# mainboard.net
KiCad netlist of a schematic drawn in EAGLE
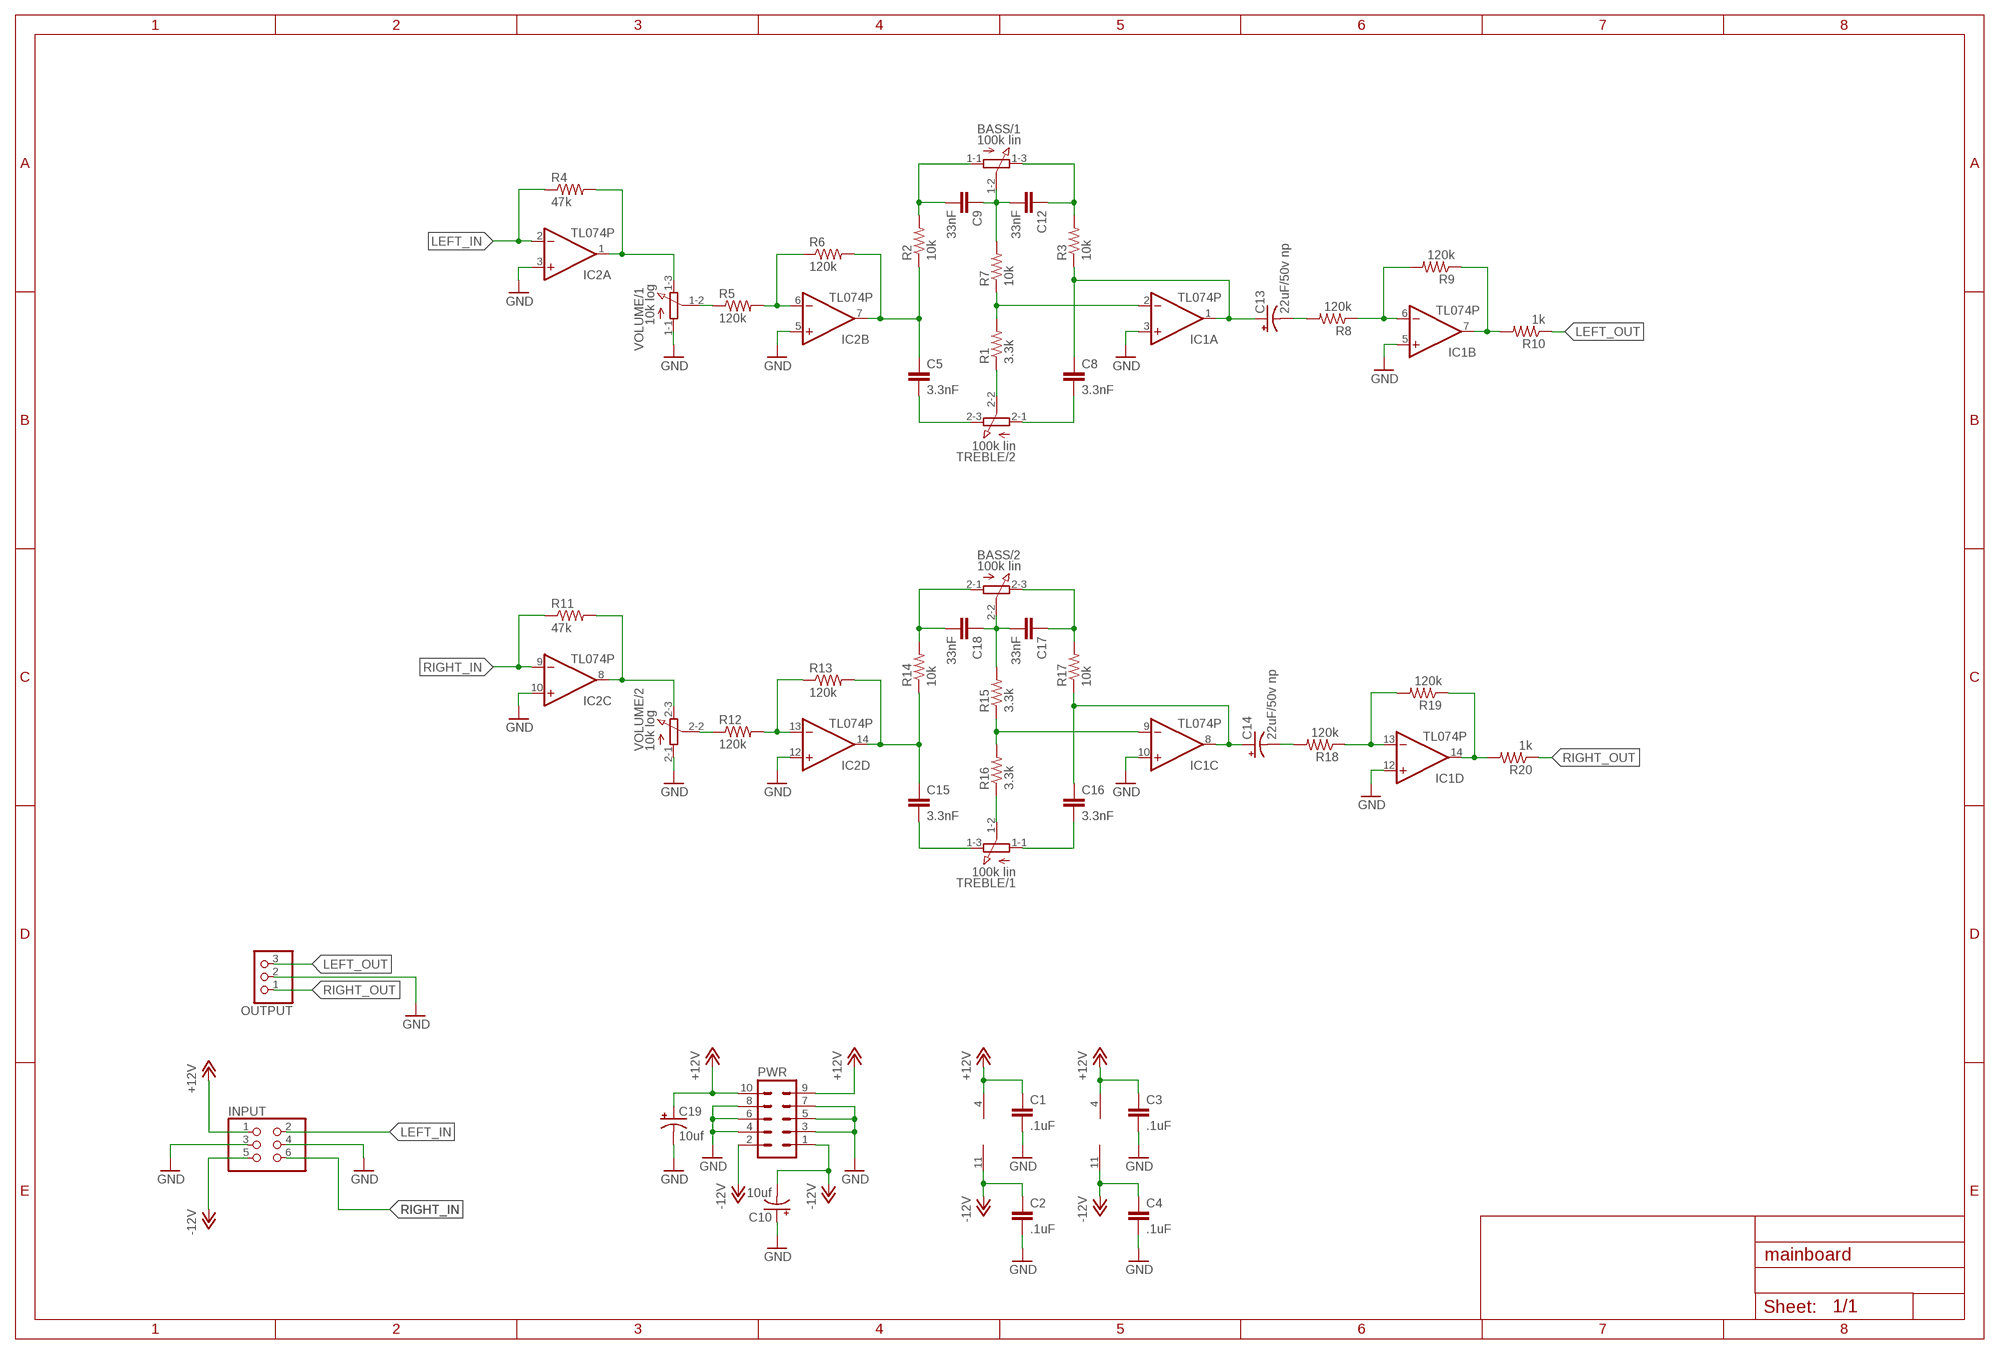
[diagram p0: schematic, sheet 1]

(export (version "E")
  (design (tool "Eeschema 10.0.6"))
  (components
    (comp (ref "BASS")
      (value "100k lin")
      (footprint "eagle-import:3RP_1610G")
      (libsource (lib "eagle-import") (part "3RP/1610G"))
    )
    (comp (ref "C1")
      (value ".1uF")
      (footprint "eagle-import:C050-024X044")
      (libsource (lib "eagle-import") (part "C-EU050-024X044"))
    )
    (comp (ref "C2")
      (value ".1uF")
      (footprint "eagle-import:C050-024X044")
      (libsource (lib "eagle-import") (part "C-EU050-024X044"))
    )
    (comp (ref "C3")
      (value ".1uF")
      (footprint "eagle-import:C050-024X044")
      (libsource (lib "eagle-import") (part "C-EU050-024X044"))
    )
    (comp (ref "C4")
      (value ".1uF")
      (footprint "eagle-import:C050-024X044")
      (libsource (lib "eagle-import") (part "C-EU050-024X044"))
    )
    (comp (ref "C5")
      (value "3.3nF")
      (footprint "eagle-import:C050-025X075")
      (libsource (lib "eagle-import") (part "C-EU050-025X075"))
    )
    (comp (ref "C8")
      (value "3.3nF")
      (footprint "eagle-import:C050-025X075")
      (libsource (lib "eagle-import") (part "C-EU050-025X075"))
    )
    (comp (ref "C9")
      (value "33nF")
      (footprint "eagle-import:C050-025X075")
      (libsource (lib "eagle-import") (part "C-EU050-025X075"))
    )
    (comp (ref "C10")
      (value "10uf")
      (footprint "eagle-import:E2,5-5")
      (libsource (lib "eagle-import") (part "resistor_CPOL-USE2.5-5"))
    )
    (comp (ref "C12")
      (value "33nF")
      (footprint "eagle-import:C050-025X075")
      (libsource (lib "eagle-import") (part "C-EU050-025X075"))
    )
    (comp (ref "C13")
      (value "22uF/50v np")
      (footprint "eagle-import:E5-10,5")
      (libsource (lib "eagle-import") (part "CPOL-USE5-10.5"))
    )
    (comp (ref "C14")
      (value "22uF/50v np")
      (footprint "eagle-import:E5-10,5")
      (libsource (lib "eagle-import") (part "CPOL-USE5-10.5"))
    )
    (comp (ref "C15")
      (value "3.3nF")
      (footprint "eagle-import:C050-025X075")
      (libsource (lib "eagle-import") (part "C-EU050-025X075"))
    )
    (comp (ref "C16")
      (value "3.3nF")
      (footprint "eagle-import:C050-025X075")
      (libsource (lib "eagle-import") (part "C-EU050-025X075"))
    )
    (comp (ref "C17")
      (value "33nF")
      (footprint "eagle-import:C050-025X075")
      (libsource (lib "eagle-import") (part "C-EU050-025X075"))
    )
    (comp (ref "C18")
      (value "33nF")
      (footprint "eagle-import:C050-025X075")
      (libsource (lib "eagle-import") (part "C-EU050-025X075"))
    )
    (comp (ref "C19")
      (value "10uf")
      (footprint "eagle-import:E2,5-5")
      (libsource (lib "eagle-import") (part "resistor_CPOL-USE2.5-5"))
    )
    (comp (ref "IC1")
      (value "TL074P")
      (footprint "eagle-import:DIL14")
      (libsource (lib "eagle-import") (part "TL074P"))
    )
    (comp (ref "IC2")
      (value "TL074P")
      (footprint "eagle-import:DIL14")
      (libsource (lib "eagle-import") (part "TL074P"))
    )
    (comp (ref "INPUT")
      (value "PINHD-2X3/90")
      (footprint "eagle-import:2X03_90")
      (libsource (lib "eagle-import") (part "PINHD-2X3/90"))
    )
    (comp (ref "OUTPUT")
      (value "PINHD-1X3")
      (footprint "eagle-import:1X03")
      (libsource (lib "eagle-import") (part "PINHD-1X3"))
    )
    (comp (ref "PWR")
      (value "ML10")
      (footprint "eagle-import:ML10")
      (libsource (lib "eagle-import") (part "ML10"))
    )
    (comp (ref "R1")
      (value "3.3k")
      (footprint "eagle-import:0207_7")
      (libsource (lib "eagle-import") (part "R-US_0207/7"))
    )
    (comp (ref "R2")
      (value "10k")
      (footprint "eagle-import:0207_7")
      (libsource (lib "eagle-import") (part "R-US_0207/7"))
    )
    (comp (ref "R3")
      (value "10k")
      (footprint "eagle-import:0207_7")
      (libsource (lib "eagle-import") (part "R-US_0207/7"))
    )
    (comp (ref "R4")
      (value "47k")
      (footprint "eagle-import:0207_7")
      (libsource (lib "eagle-import") (part "R-US_0207/7"))
    )
    (comp (ref "R5")
      (value "120k")
      (footprint "eagle-import:0207_7")
      (libsource (lib "eagle-import") (part "R-US_0207/7"))
    )
    (comp (ref "R6")
      (value "120k")
      (footprint "eagle-import:0207_7")
      (libsource (lib "eagle-import") (part "R-US_0207/7"))
    )
    (comp (ref "R7")
      (value "10k")
      (footprint "eagle-import:0207_7")
      (libsource (lib "eagle-import") (part "R-US_0207/7"))
    )
    (comp (ref "R8")
      (value "120k")
      (footprint "eagle-import:0207_7")
      (libsource (lib "eagle-import") (part "R-US_0207/7"))
    )
    (comp (ref "R9")
      (value "120k")
      (footprint "eagle-import:0207_7")
      (libsource (lib "eagle-import") (part "R-US_0207/7"))
    )
    (comp (ref "R10")
      (value "1k")
      (footprint "eagle-import:0207_7")
      (libsource (lib "eagle-import") (part "R-US_0207/7"))
    )
    (comp (ref "R11")
      (value "47k")
      (footprint "eagle-import:0207_7")
      (libsource (lib "eagle-import") (part "R-US_0207/7"))
    )
    (comp (ref "R12")
      (value "120k")
      (footprint "eagle-import:0207_7")
      (libsource (lib "eagle-import") (part "R-US_0207/7"))
    )
    (comp (ref "R13")
      (value "120k")
      (footprint "eagle-import:0207_7")
      (libsource (lib "eagle-import") (part "R-US_0207/7"))
    )
    (comp (ref "R14")
      (value "10k")
      (footprint "eagle-import:0207_7")
      (libsource (lib "eagle-import") (part "R-US_0207/7"))
    )
    (comp (ref "R15")
      (value "3.3k")
      (footprint "eagle-import:0207_7")
      (libsource (lib "eagle-import") (part "R-US_0207/7"))
    )
    (comp (ref "R16")
      (value "3.3k")
      (footprint "eagle-import:0207_7")
      (libsource (lib "eagle-import") (part "R-US_0207/7"))
    )
    (comp (ref "R17")
      (value "10k")
      (footprint "eagle-import:0207_7")
      (libsource (lib "eagle-import") (part "R-US_0207/7"))
    )
    (comp (ref "R18")
      (value "120k")
      (footprint "eagle-import:0207_7")
      (libsource (lib "eagle-import") (part "R-US_0207/7"))
    )
    (comp (ref "R19")
      (value "120k")
      (footprint "eagle-import:0207_7")
      (libsource (lib "eagle-import") (part "R-US_0207/7"))
    )
    (comp (ref "R20")
      (value "1k")
      (footprint "eagle-import:0207_7")
      (libsource (lib "eagle-import") (part "R-US_0207/7"))
    )
    (comp (ref "TREBLE")
      (value "100k lin")
      (footprint "eagle-import:3RP_1610G")
      (libsource (lib "eagle-import") (part "3RP/1610G"))
    )
    (comp (ref "VOLUME")
      (value "10k log")
      (footprint "eagle-import:3RP_1610G")
      (libsource (lib "eagle-import") (part "3RP/1610G"))
    )
  )
  (nets
    (net (code "1") (name "+12V") (class "Default")
      (node (ref "C1") (pin "1") (pinfunction "1_1") (pintype "passive"))
      (node (ref "C19") (pin "+") (pinfunction "+_+") (pintype "passive"))
      (node (ref "C3") (pin "1") (pinfunction "1_1") (pintype "passive"))
      (node (ref "IC1") (pin "4") (pinfunction "V+_4") (pintype "power_in"))
      (node (ref "IC2") (pin "4") (pinfunction "V+_4") (pintype "power_in"))
      (node (ref "INPUT") (pin "1") (pinfunction "1_1") (pintype "passive"))
      (node (ref "PWR") (pin "10") (pinfunction "10_10") (pintype "passive"))
      (node (ref "PWR") (pin "9") (pinfunction "9_9") (pintype "passive"))
    )
    (net (code "2") (name "-12V") (class "Default")
      (node (ref "C10") (pin "-") (pinfunction "-_-") (pintype "passive"))
      (node (ref "C2") (pin "1") (pinfunction "1_1") (pintype "passive"))
      (node (ref "C4") (pin "1") (pinfunction "1_1") (pintype "passive"))
      (node (ref "IC1") (pin "11") (pinfunction "V-_11") (pintype "power_in"))
      (node (ref "IC2") (pin "11") (pinfunction "V-_11") (pintype "power_in"))
      (node (ref "INPUT") (pin "5") (pinfunction "5_5") (pintype "passive"))
      (node (ref "PWR") (pin "1") (pinfunction "1_1") (pintype "passive"))
      (node (ref "PWR") (pin "2") (pinfunction "2_2") (pintype "passive"))
    )
    (net (code "3") (name "GND") (class "Default")
      (node (ref "C1") (pin "2") (pinfunction "2_2") (pintype "passive"))
      (node (ref "C10") (pin "+") (pinfunction "+_+") (pintype "passive"))
      (node (ref "C19") (pin "-") (pinfunction "-_-") (pintype "passive"))
      (node (ref "C2") (pin "2") (pinfunction "2_2") (pintype "passive"))
      (node (ref "C3") (pin "2") (pinfunction "2_2") (pintype "passive"))
      (node (ref "C4") (pin "2") (pinfunction "2_2") (pintype "passive"))
      (node (ref "IC1") (pin "10") (pinfunction "+IN_10") (pintype "input"))
      (node (ref "IC1") (pin "12") (pinfunction "+IN_12") (pintype "input"))
      (node (ref "IC1") (pin "3") (pinfunction "+IN_3") (pintype "input"))
      (node (ref "IC1") (pin "5") (pinfunction "+IN_5") (pintype "input"))
      (node (ref "IC2") (pin "10") (pinfunction "+IN_10") (pintype "input"))
      (node (ref "IC2") (pin "12") (pinfunction "+IN_12") (pintype "input"))
      (node (ref "IC2") (pin "3") (pinfunction "+IN_3") (pintype "input"))
      (node (ref "IC2") (pin "5") (pinfunction "+IN_5") (pintype "input"))
      (node (ref "INPUT") (pin "3") (pinfunction "3_3") (pintype "passive"))
      (node (ref "INPUT") (pin "4") (pinfunction "4_4") (pintype "passive"))
      (node (ref "OUTPUT") (pin "2") (pinfunction "2_2") (pintype "passive"))
      (node (ref "PWR") (pin "3") (pinfunction "3_3") (pintype "passive"))
      (node (ref "PWR") (pin "4") (pinfunction "4_4") (pintype "passive"))
      (node (ref "PWR") (pin "5") (pinfunction "5_5") (pintype "passive"))
      (node (ref "PWR") (pin "6") (pinfunction "6_6") (pintype "passive"))
      (node (ref "PWR") (pin "7") (pinfunction "7_7") (pintype "passive"))
      (node (ref "PWR") (pin "8") (pinfunction "8_8") (pintype "passive"))
      (node (ref "VOLUME") (pin "1-1") (pinfunction "A_1-1") (pintype "passive"))
      (node (ref "VOLUME") (pin "2-1") (pinfunction "A_2-1") (pintype "passive"))
    )
    (net (code "4") (name "LEFT_IN") (class "Default")
      (node (ref "IC2") (pin "2") (pinfunction "-IN_2") (pintype "input"))
      (node (ref "INPUT") (pin "2") (pinfunction "2_2") (pintype "passive"))
      (node (ref "R4") (pin "1") (pinfunction "1_1") (pintype "passive"))
    )
    (net (code "5") (name "LEFT_OUT") (class "Default")
      (node (ref "OUTPUT") (pin "3") (pinfunction "3_3") (pintype "passive"))
      (node (ref "R10") (pin "1") (pinfunction "1_1") (pintype "passive"))
    )
    (net (code "6") (name "Net-(BASSA-A)") (class "Default")
      (node (ref "BASS") (pin "1-1") (pinfunction "A_1-1") (pintype "passive"))
      (node (ref "C9") (pin "2") (pinfunction "2_2") (pintype "passive"))
      (node (ref "R2") (pin "2") (pinfunction "2_2") (pintype "passive"))
    )
    (net (code "7") (name "Net-(BASSA-E)") (class "Default")
      (node (ref "BASS") (pin "1-3") (pinfunction "E_1-3") (pintype "passive"))
      (node (ref "C12") (pin "1") (pinfunction "1_1") (pintype "passive"))
      (node (ref "R3") (pin "2") (pinfunction "2_2") (pintype "passive"))
    )
    (net (code "8") (name "Net-(BASSA-S)") (class "Default")
      (node (ref "BASS") (pin "1-2") (pinfunction "S_1-2") (pintype "passive"))
      (node (ref "C12") (pin "2") (pinfunction "2_2") (pintype "passive"))
      (node (ref "C9") (pin "1") (pinfunction "1_1") (pintype "passive"))
      (node (ref "R7") (pin "2") (pinfunction "2_2") (pintype "passive"))
    )
    (net (code "9") (name "Net-(BASSB-A)") (class "Default")
      (node (ref "BASS") (pin "2-1") (pinfunction "A_2-1") (pintype "passive"))
      (node (ref "C18") (pin "2") (pinfunction "2_2") (pintype "passive"))
      (node (ref "R14") (pin "2") (pinfunction "2_2") (pintype "passive"))
    )
    (net (code "10") (name "Net-(BASSB-E)") (class "Default")
      (node (ref "BASS") (pin "2-3") (pinfunction "E_2-3") (pintype "passive"))
      (node (ref "C17") (pin "1") (pinfunction "1_1") (pintype "passive"))
      (node (ref "R17") (pin "2") (pinfunction "2_2") (pintype "passive"))
    )
    (net (code "11") (name "Net-(BASSB-S)") (class "Default")
      (node (ref "BASS") (pin "2-2") (pinfunction "S_2-2") (pintype "passive"))
      (node (ref "C17") (pin "2") (pinfunction "2_2") (pintype "passive"))
      (node (ref "C18") (pin "1") (pinfunction "1_1") (pintype "passive"))
      (node (ref "R15") (pin "2") (pinfunction "2_2") (pintype "passive"))
    )
    (net (code "12") (name "Net-(C13-Pad-)") (class "Default")
      (node (ref "C13") (pin "-") (pinfunction "-_-") (pintype "passive"))
      (node (ref "R8") (pin "2") (pinfunction "2_2") (pintype "passive"))
    )
    (net (code "13") (name "Net-(C14-Pad-)") (class "Default")
      (node (ref "C14") (pin "-") (pinfunction "-_-") (pintype "passive"))
      (node (ref "R18") (pin "2") (pinfunction "2_2") (pintype "passive"))
    )
    (net (code "14") (name "Net-(IC1A--IN)") (class "Default")
      (node (ref "IC1") (pin "2") (pinfunction "-IN_2") (pintype "input"))
      (node (ref "R1") (pin "2") (pinfunction "2_2") (pintype "passive"))
      (node (ref "R7") (pin "1") (pinfunction "1_1") (pintype "passive"))
    )
    (net (code "15") (name "Net-(IC1A-OUT)") (class "Default")
      (node (ref "C13") (pin "+") (pinfunction "+_+") (pintype "passive"))
      (node (ref "C8") (pin "1") (pinfunction "1_1") (pintype "passive"))
      (node (ref "IC1") (pin "1") (pinfunction "OUT_1") (pintype "output"))
      (node (ref "R3") (pin "1") (pinfunction "1_1") (pintype "passive"))
    )
    (net (code "16") (name "Net-(IC1B--IN)") (class "Default")
      (node (ref "IC1") (pin "6") (pinfunction "-IN_6") (pintype "input"))
      (node (ref "R8") (pin "1") (pinfunction "1_1") (pintype "passive"))
      (node (ref "R9") (pin "2") (pinfunction "2_2") (pintype "passive"))
    )
    (net (code "17") (name "Net-(IC1B-OUT)") (class "Default")
      (node (ref "IC1") (pin "7") (pinfunction "OUT_7") (pintype "output"))
      (node (ref "R10") (pin "2") (pinfunction "2_2") (pintype "passive"))
      (node (ref "R9") (pin "1") (pinfunction "1_1") (pintype "passive"))
    )
    (net (code "18") (name "Net-(IC1C--IN)") (class "Default")
      (node (ref "IC1") (pin "9") (pinfunction "-IN_9") (pintype "input"))
      (node (ref "R15") (pin "1") (pinfunction "1_1") (pintype "passive"))
      (node (ref "R16") (pin "2") (pinfunction "2_2") (pintype "passive"))
    )
    (net (code "19") (name "Net-(IC1C-OUT)") (class "Default")
      (node (ref "C14") (pin "+") (pinfunction "+_+") (pintype "passive"))
      (node (ref "C16") (pin "1") (pinfunction "1_1") (pintype "passive"))
      (node (ref "IC1") (pin "8") (pinfunction "OUT_8") (pintype "output"))
      (node (ref "R17") (pin "1") (pinfunction "1_1") (pintype "passive"))
    )
    (net (code "20") (name "Net-(IC1D--IN)") (class "Default")
      (node (ref "IC1") (pin "13") (pinfunction "-IN_13") (pintype "input"))
      (node (ref "R18") (pin "1") (pinfunction "1_1") (pintype "passive"))
      (node (ref "R19") (pin "2") (pinfunction "2_2") (pintype "passive"))
    )
    (net (code "21") (name "Net-(IC1D-OUT)") (class "Default")
      (node (ref "IC1") (pin "14") (pinfunction "OUT_14") (pintype "output"))
      (node (ref "R19") (pin "1") (pinfunction "1_1") (pintype "passive"))
      (node (ref "R20") (pin "2") (pinfunction "2_2") (pintype "passive"))
    )
    (net (code "22") (name "Net-(IC2A-OUT)") (class "Default")
      (node (ref "IC2") (pin "1") (pinfunction "OUT_1") (pintype "output"))
      (node (ref "R4") (pin "2") (pinfunction "2_2") (pintype "passive"))
      (node (ref "VOLUME") (pin "1-3") (pinfunction "E_1-3") (pintype "passive"))
    )
    (net (code "23") (name "Net-(IC2B--IN)") (class "Default")
      (node (ref "IC2") (pin "6") (pinfunction "-IN_6") (pintype "input"))
      (node (ref "R5") (pin "2") (pinfunction "2_2") (pintype "passive"))
      (node (ref "R6") (pin "1") (pinfunction "1_1") (pintype "passive"))
    )
    (net (code "24") (name "Net-(IC2B-OUT)") (class "Default")
      (node (ref "C5") (pin "1") (pinfunction "1_1") (pintype "passive"))
      (node (ref "IC2") (pin "7") (pinfunction "OUT_7") (pintype "output"))
      (node (ref "R2") (pin "1") (pinfunction "1_1") (pintype "passive"))
      (node (ref "R6") (pin "2") (pinfunction "2_2") (pintype "passive"))
    )
    (net (code "25") (name "Net-(IC2C-OUT)") (class "Default")
      (node (ref "IC2") (pin "8") (pinfunction "OUT_8") (pintype "output"))
      (node (ref "R11") (pin "2") (pinfunction "2_2") (pintype "passive"))
      (node (ref "VOLUME") (pin "2-3") (pinfunction "E_2-3") (pintype "passive"))
    )
    (net (code "26") (name "Net-(IC2D--IN)") (class "Default")
      (node (ref "IC2") (pin "13") (pinfunction "-IN_13") (pintype "input"))
      (node (ref "R12") (pin "2") (pinfunction "2_2") (pintype "passive"))
      (node (ref "R13") (pin "1") (pinfunction "1_1") (pintype "passive"))
    )
    (net (code "27") (name "Net-(IC2D-OUT)") (class "Default")
      (node (ref "C15") (pin "1") (pinfunction "1_1") (pintype "passive"))
      (node (ref "IC2") (pin "14") (pinfunction "OUT_14") (pintype "output"))
      (node (ref "R13") (pin "2") (pinfunction "2_2") (pintype "passive"))
      (node (ref "R14") (pin "1") (pinfunction "1_1") (pintype "passive"))
    )
    (net (code "28") (name "Net-(TREBLEA-A)") (class "Default")
      (node (ref "C16") (pin "2") (pinfunction "2_2") (pintype "passive"))
      (node (ref "TREBLE") (pin "1-1") (pinfunction "A_1-1") (pintype "passive"))
    )
    (net (code "29") (name "Net-(TREBLEA-E)") (class "Default")
      (node (ref "C15") (pin "2") (pinfunction "2_2") (pintype "passive"))
      (node (ref "TREBLE") (pin "1-3") (pinfunction "E_1-3") (pintype "passive"))
    )
    (net (code "30") (name "Net-(TREBLEA-S)") (class "Default")
      (node (ref "R16") (pin "1") (pinfunction "1_1") (pintype "passive"))
      (node (ref "TREBLE") (pin "1-2") (pinfunction "S_1-2") (pintype "passive"))
    )
    (net (code "31") (name "Net-(TREBLEB-A)") (class "Default")
      (node (ref "C8") (pin "2") (pinfunction "2_2") (pintype "passive"))
      (node (ref "TREBLE") (pin "2-1") (pinfunction "A_2-1") (pintype "passive"))
    )
    (net (code "32") (name "Net-(TREBLEB-E)") (class "Default")
      (node (ref "C5") (pin "2") (pinfunction "2_2") (pintype "passive"))
      (node (ref "TREBLE") (pin "2-3") (pinfunction "E_2-3") (pintype "passive"))
    )
    (net (code "33") (name "Net-(TREBLEB-S)") (class "Default")
      (node (ref "R1") (pin "1") (pinfunction "1_1") (pintype "passive"))
      (node (ref "TREBLE") (pin "2-2") (pinfunction "S_2-2") (pintype "passive"))
    )
    (net (code "34") (name "Net-(VOLUMEA-S)") (class "Default")
      (node (ref "R5") (pin "1") (pinfunction "1_1") (pintype "passive"))
      (node (ref "VOLUME") (pin "1-2") (pinfunction "S_1-2") (pintype "passive"))
    )
    (net (code "35") (name "Net-(VOLUMEB-S)") (class "Default")
      (node (ref "R12") (pin "1") (pinfunction "1_1") (pintype "passive"))
      (node (ref "VOLUME") (pin "2-2") (pinfunction "S_2-2") (pintype "passive"))
    )
    (net (code "36") (name "RIGHT_IN") (class "Default")
      (node (ref "IC2") (pin "9") (pinfunction "-IN_9") (pintype "input"))
      (node (ref "INPUT") (pin "6") (pinfunction "6_6") (pintype "passive"))
      (node (ref "R11") (pin "1") (pinfunction "1_1") (pintype "passive"))
    )
    (net (code "37") (name "RIGHT_OUT") (class "Default")
      (node (ref "OUTPUT") (pin "1") (pinfunction "1_1") (pintype "passive"))
      (node (ref "R20") (pin "1") (pinfunction "1_1") (pintype "passive"))
    )
  )
)
